# RX-FM-Radio-Simple-Dip1.net
KiCad netlist of a schematic drawn in EAGLE
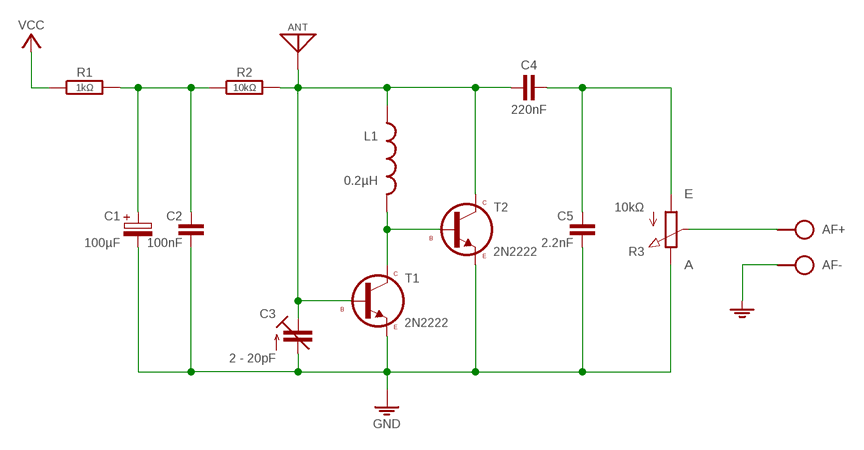
[diagram p0: schematic, sheet 1]

(export (version "E")
  (design (tool "Eeschema 10.0.6"))
  (components
    (comp (ref "AF")
      (value "SPAD+--+")
      (footprint "eagle-import:SPAD-+")
      (libsource (lib "eagle-import") (part "SPAD+--+"))
    )
    (comp (ref "ANT")
      (value "ANT")
      (footprint "eagle-import:SPAD")
      (libsource (lib "eagle-import") (part "ANT"))
    )
    (comp (ref "BAT")
      (value "VCC_GNDL")
      (footprint "eagle-import:SPAD-+")
      (libsource (lib "eagle-import") (part "VCC_GNDL"))
    )
    (comp (ref "C1")
      (value "100µF")
      (footprint "eagle-import:E2,5-5_V")
      (libsource (lib "eagle-import") (part "CPOLE2,5-5/V"))
    )
    (comp (ref "C2")
      (value "100nF")
      (footprint "eagle-import:C050-020X036_V")
      (libsource (lib "eagle-import") (part "C050-020X036/V"))
    )
    (comp (ref "C3")
      (value "2 - 20pF")
      (footprint "eagle-import:TRIM-2222-808")
      (libsource (lib "eagle-import") (part "C-TR-PH201272222-808-2PIND"))
    )
    (comp (ref "C4")
      (value "220nF")
      (footprint "eagle-import:C050-020X044")
      (libsource (lib "eagle-import") (part "C-H050-020X044"))
    )
    (comp (ref "C5")
      (value "2.2nF")
      (footprint "eagle-import:C025-020X036")
      (libsource (lib "eagle-import") (part "C025-020X036"))
    )
    (comp (ref "L1")
      (value "0.2µH")
      (footprint "eagle-import:L-10_10Y")
      (libsource (lib "eagle-import") (part "L10/10Y"))
    )
    (comp (ref "R1")
      (value "1kΩ")
      (footprint "eagle-import:0204_10")
      (libsource (lib "eagle-import") (part "R-H0204/10"))
    )
    (comp (ref "R2")
      (value "10kΩ")
      (footprint "eagle-import:0204_10")
      (libsource (lib "eagle-import") (part "R-H0204/10"))
    )
    (comp (ref "R3")
      (value "10kΩ")
      (footprint "eagle-import:CONN-3P")
      (libsource (lib "eagle-import") (part "POT-3P"))
    )
    (comp (ref "T1")
      (value "2N2222")
      (footprint "eagle-import:TO92")
      (libsource (lib "eagle-import") (part "2N2222"))
    )
    (comp (ref "T2")
      (value "2N2222")
      (footprint "eagle-import:TO92")
      (libsource (lib "eagle-import") (part "2N2222"))
    )
  )
  (nets
    (net (code "1") (name "GND") (class "Default")
      (node (ref "AF") (pin "1") (pinfunction "P$1_1") (pintype "passive"))
      (node (ref "BAT") (pin "1") (pinfunction "GND_1") (pintype "power_in"))
      (node (ref "C1") (pin "-") (pinfunction "-_-") (pintype "passive"))
      (node (ref "C2") (pin "2") (pinfunction "2_2") (pintype "passive"))
      (node (ref "C3") (pin "2") (pinfunction "A_2") (pintype "passive"))
      (node (ref "C5") (pin "2") (pinfunction "2_2") (pintype "passive"))
      (node (ref "R3") (pin "3") (pinfunction "E_3") (pintype "passive"))
      (node (ref "T1") (pin "1") (pinfunction "E_1") (pintype "passive"))
      (node (ref "T2") (pin "1") (pinfunction "E_1") (pintype "passive"))
    )
    (net (code "2") (name "Net-(AFA-P$1)") (class "Default")
      (node (ref "AF") (pin "2") (pinfunction "P$1_2") (pintype "passive"))
      (node (ref "R3") (pin "2") (pinfunction "S_2") (pintype "passive"))
    )
    (net (code "3") (name "Net-(BATA-VCC)") (class "Default")
      (node (ref "BAT") (pin "2") (pinfunction "VCC_2") (pintype "power_in"))
      (node (ref "R1") (pin "1") (pinfunction "1_1") (pintype "passive"))
    )
    (net (code "4") (name "Net-(C1-Pad+)") (class "Default")
      (node (ref "C1") (pin "+") (pinfunction "+_+") (pintype "passive"))
      (node (ref "C2") (pin "1") (pinfunction "1_1") (pintype "passive"))
      (node (ref "R1") (pin "2") (pinfunction "2_2") (pintype "passive"))
      (node (ref "R2") (pin "1") (pinfunction "1_1") (pintype "passive"))
    )
    (net (code "5") (name "Net-(C3-E)") (class "Default")
      (node (ref "ANT") (pin "1") (pinfunction "1_1") (pintype "output"))
      (node (ref "C3") (pin "3") (pinfunction "E_3") (pintype "passive"))
      (node (ref "C4") (pin "1") (pinfunction "1_1") (pintype "passive"))
      (node (ref "L1") (pin "P$1") (pinfunction "1_P$1") (pintype "passive"))
      (node (ref "R2") (pin "2") (pinfunction "2_2") (pintype "passive"))
      (node (ref "T1") (pin "2") (pinfunction "B_2") (pintype "passive"))
      (node (ref "T2") (pin "3") (pinfunction "C_3") (pintype "passive"))
    )
    (net (code "6") (name "Net-(L1-2)") (class "Default")
      (node (ref "L1") (pin "P$2") (pinfunction "2_P$2") (pintype "passive"))
      (node (ref "T1") (pin "3") (pinfunction "C_3") (pintype "passive"))
      (node (ref "T2") (pin "2") (pinfunction "B_2") (pintype "passive"))
    )
    (net (code "7") (name "Net-(R3-A)") (class "Default")
      (node (ref "C4") (pin "2") (pinfunction "2_2") (pintype "passive"))
      (node (ref "C5") (pin "1") (pinfunction "1_1") (pintype "passive"))
      (node (ref "R3") (pin "1") (pinfunction "A_1") (pintype "passive"))
    )
  )
)
